# raspberrypi_isp_tool.net
KiCad netlist of a schematic drawn in EAGLE
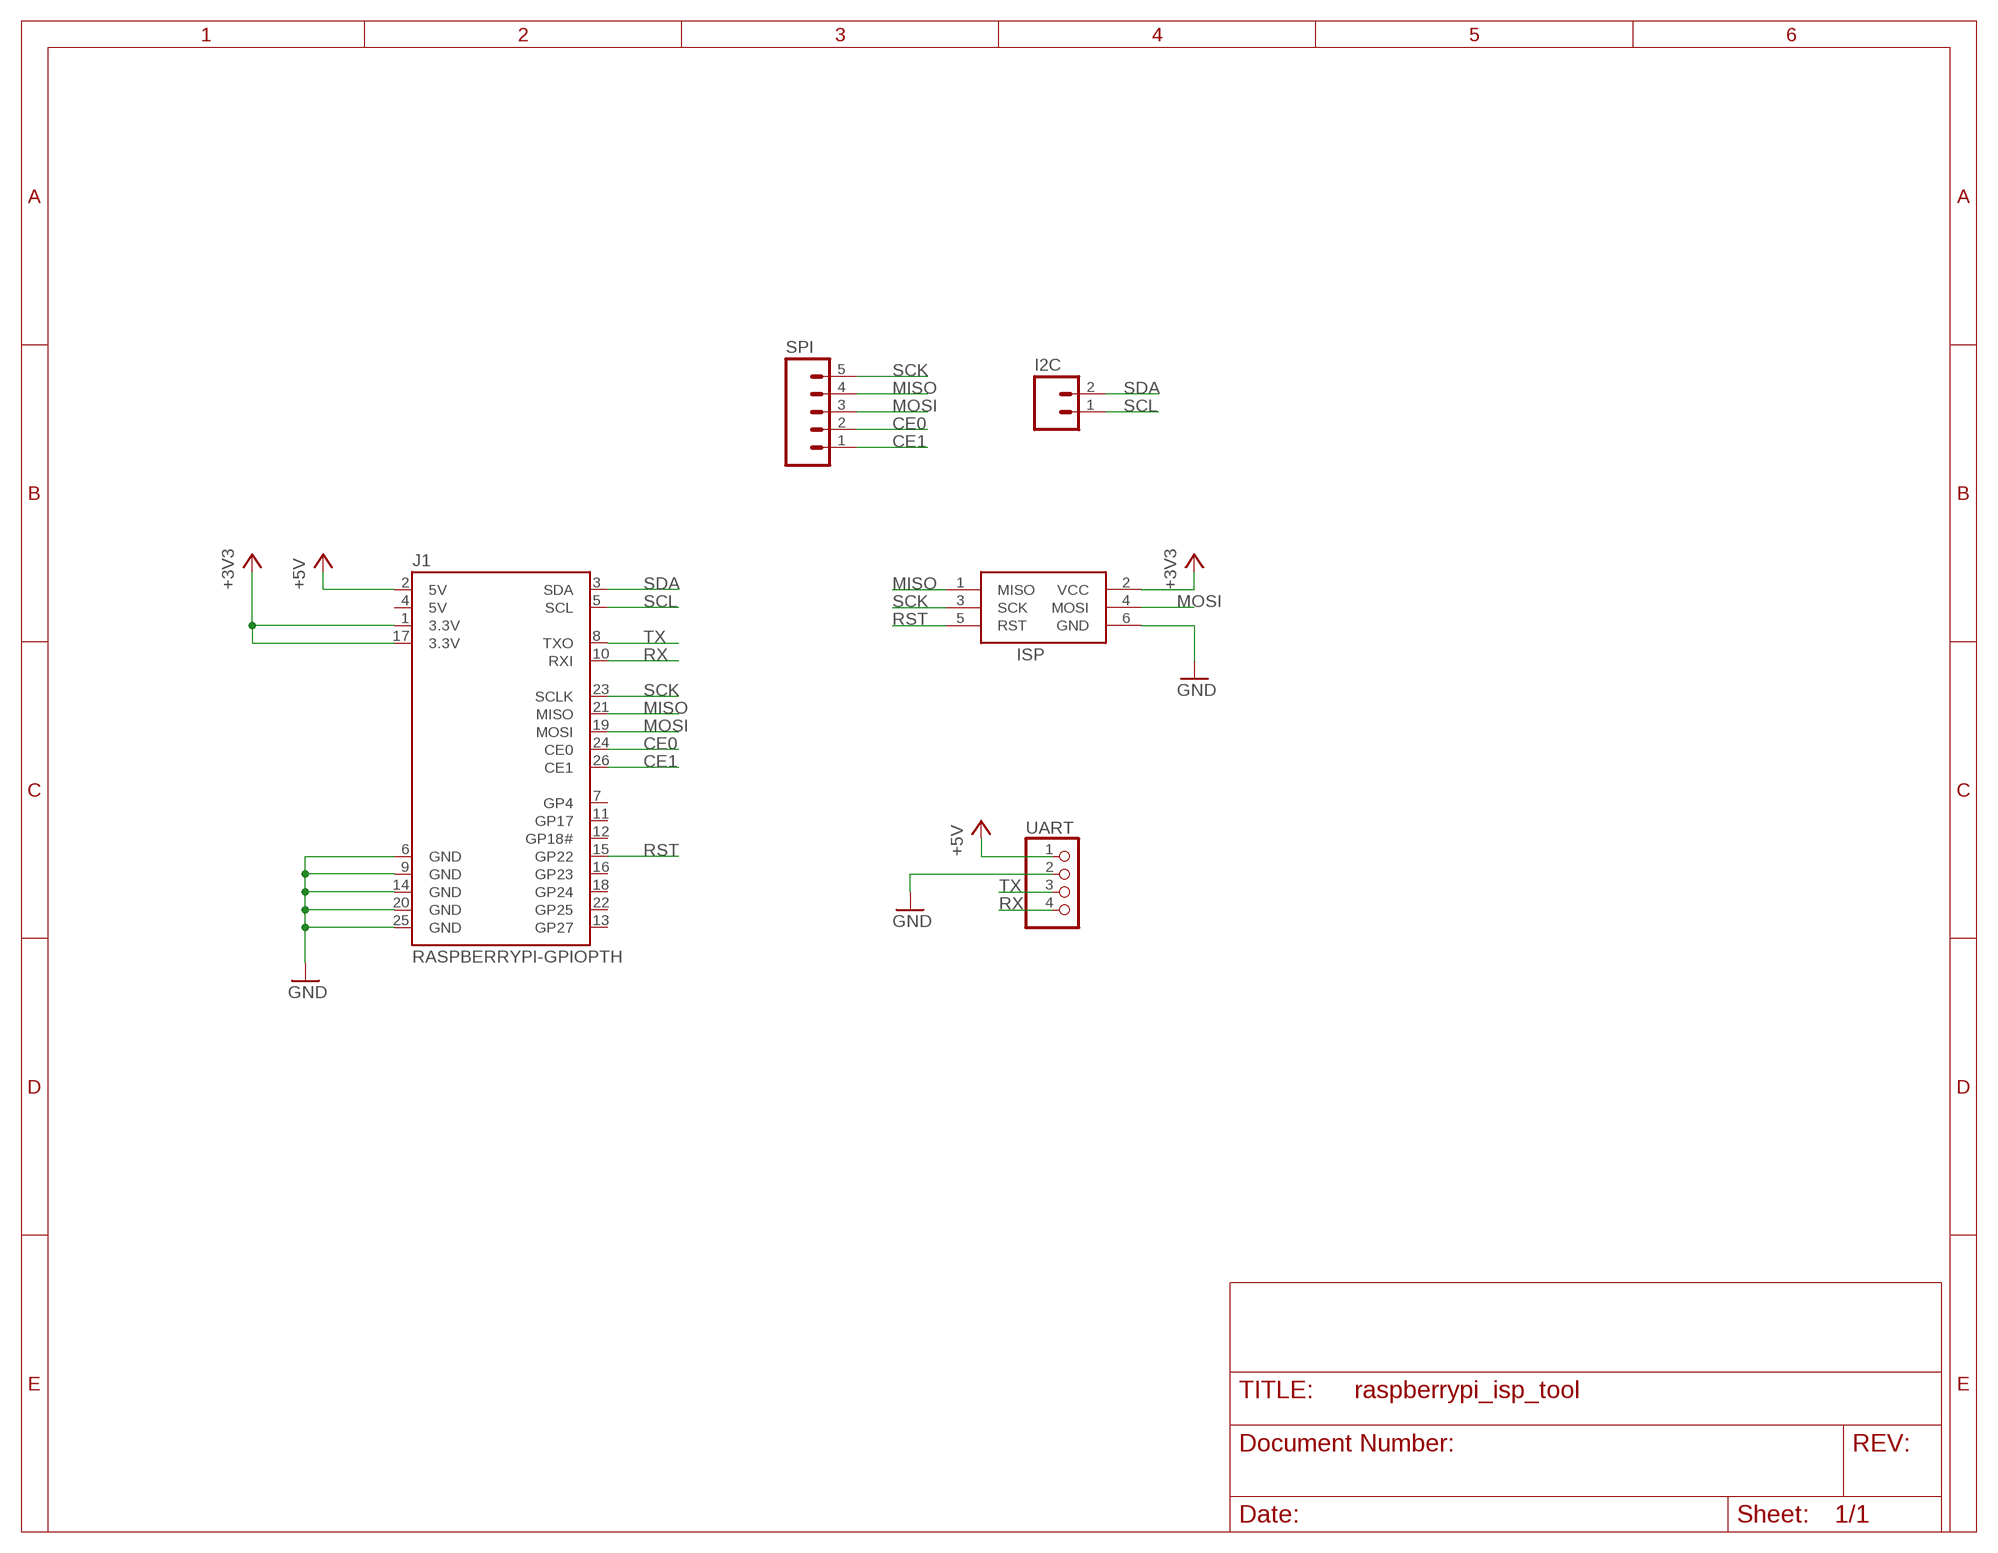
[diagram p0: schematic, sheet 1]

(export (version "E")
  (design (tool "Eeschema 10.0.6"))
  (components
    (comp (ref "I2C")
      (value "M02PTH")
      (footprint "eagle-import:1X02")
      (libsource (lib "eagle-import") (part "M02PTH"))
    )
    (comp (ref "ISP")
      (value "AVRISP-6")
      (footprint "eagle-import:AVRISP")
      (libsource (lib "eagle-import") (part "AVRISP-6"))
    )
    (comp (ref "J1")
      (value "RASPBERRYPI-GPIOPTH")
      (footprint "eagle-import:2X13-SHROUDED")
      (libsource (lib "eagle-import") (part "RASPBERRYPI-GPIOPTH"))
    )
    (comp (ref "SPI")
      (value "M05PTH")
      (footprint "eagle-import:1X05")
      (libsource (lib "eagle-import") (part "M05PTH"))
    )
    (comp (ref "UART")
      (value "PINHD-1X4")
      (footprint "eagle-import:1X04")
      (libsource (lib "eagle-import") (part "PINHD-1X4"))
    )
  )
  (nets
    (net (code "1") (name "+3V3") (class "Default")
      (node (ref "ISP") (pin "2") (pinfunction "VCC_2") (pintype "power_in"))
      (node (ref "J1") (pin "1") (pinfunction "3.3V_1") (pintype "power_in"))
      (node (ref "J1") (pin "17") (pinfunction "3.3V_17") (pintype "power_in"))
    )
    (net (code "2") (name "+5V") (class "Default")
      (node (ref "J1") (pin "2") (pinfunction "5V_2") (pintype "power_in"))
      (node (ref "UART") (pin "1") (pinfunction "1_1") (pintype "passive"))
    )
    (net (code "3") (name "/5V") (class "Default")
      (node (ref "J1") (pin "4") (pinfunction "5V_4") (pintype "power_in"))
    )
    (net (code "4") (name "/CE0") (class "Default")
      (node (ref "J1") (pin "24") (pinfunction "CE0_24") (pintype "output"))
      (node (ref "SPI") (pin "2") (pinfunction "2_2") (pintype "passive"))
    )
    (net (code "5") (name "/CE1") (class "Default")
      (node (ref "J1") (pin "26") (pinfunction "CE1_26") (pintype "output"))
      (node (ref "SPI") (pin "1") (pinfunction "1_1") (pintype "passive"))
    )
    (net (code "6") (name "/MISO") (class "Default")
      (node (ref "ISP") (pin "1") (pinfunction "MISO_1") (pintype "input"))
      (node (ref "J1") (pin "21") (pinfunction "MISO_21") (pintype "input"))
      (node (ref "SPI") (pin "4") (pinfunction "4_4") (pintype "passive"))
    )
    (net (code "7") (name "/MOSI") (class "Default")
      (node (ref "ISP") (pin "4") (pinfunction "MOSI_4") (pintype "output"))
      (node (ref "J1") (pin "19") (pinfunction "MOSI_19") (pintype "output"))
      (node (ref "SPI") (pin "3") (pinfunction "3_3") (pintype "passive"))
    )
    (net (code "8") (name "/RST") (class "Default")
      (node (ref "ISP") (pin "5") (pinfunction "RST_5") (pintype "output"))
      (node (ref "J1") (pin "15") (pinfunction "GP22_15") (pintype "bidirectional"))
    )
    (net (code "9") (name "/RX") (class "Default")
      (node (ref "J1") (pin "10") (pinfunction "RXI_10") (pintype "input"))
      (node (ref "UART") (pin "4") (pinfunction "4_4") (pintype "passive"))
    )
    (net (code "10") (name "/SCK") (class "Default")
      (node (ref "ISP") (pin "3") (pinfunction "SCK_3") (pintype "output"))
      (node (ref "J1") (pin "23") (pinfunction "SCLK_23") (pintype "output"))
      (node (ref "SPI") (pin "5") (pinfunction "5_5") (pintype "passive"))
    )
    (net (code "11") (name "/SCL") (class "Default")
      (node (ref "I2C") (pin "1") (pinfunction "1_1") (pintype "passive"))
      (node (ref "J1") (pin "5") (pinfunction "SCL_5") (pintype "bidirectional"))
    )
    (net (code "12") (name "/SDA") (class "Default")
      (node (ref "I2C") (pin "2") (pinfunction "2_2") (pintype "passive"))
      (node (ref "J1") (pin "3") (pinfunction "SDA_3") (pintype "bidirectional"))
    )
    (net (code "13") (name "/TX") (class "Default")
      (node (ref "J1") (pin "8") (pinfunction "TXO_8") (pintype "output"))
      (node (ref "UART") (pin "3") (pinfunction "3_3") (pintype "passive"))
    )
    (net (code "14") (name "GND") (class "Default")
      (node (ref "ISP") (pin "6") (pinfunction "GND_6") (pintype "power_in"))
      (node (ref "J1") (pin "14") (pinfunction "GND_14") (pintype "power_in"))
      (node (ref "J1") (pin "20") (pinfunction "GND_20") (pintype "power_in"))
      (node (ref "J1") (pin "25") (pinfunction "GND_25") (pintype "power_in"))
      (node (ref "J1") (pin "6") (pinfunction "GND_6") (pintype "power_in"))
      (node (ref "J1") (pin "9") (pinfunction "GND_9") (pintype "power_in"))
      (node (ref "UART") (pin "2") (pinfunction "2_2") (pintype "passive"))
    )
    (net (code "15") (name "unconnected-(J1-GP4-Pad7)") (class "Default")
      (node (ref "J1") (pin "7") (pinfunction "GP4_7") (pintype "bidirectional"))
    )
    (net (code "16") (name "unconnected-(J1-GP17-Pad11)") (class "Default")
      (node (ref "J1") (pin "11") (pinfunction "GP17_11") (pintype "bidirectional"))
    )
    (net (code "17") (name "unconnected-(J1-GP18#-Pad12)") (class "Default")
      (node (ref "J1") (pin "12") (pinfunction "GP18#_12") (pintype "bidirectional"))
    )
    (net (code "18") (name "unconnected-(J1-GP23-Pad16)") (class "Default")
      (node (ref "J1") (pin "16") (pinfunction "GP23_16") (pintype "bidirectional"))
    )
    (net (code "19") (name "unconnected-(J1-GP24-Pad18)") (class "Default")
      (node (ref "J1") (pin "18") (pinfunction "GP24_18") (pintype "bidirectional"))
    )
    (net (code "20") (name "unconnected-(J1-GP25-Pad22)") (class "Default")
      (node (ref "J1") (pin "22") (pinfunction "GP25_22") (pintype "bidirectional"))
    )
    (net (code "21") (name "unconnected-(J1-GP27-Pad13)") (class "Default")
      (node (ref "J1") (pin "13") (pinfunction "GP27_13") (pintype "bidirectional"))
    )
  )
)
